# Vibration-Motor.net
KiCad netlist of a schematic drawn in Altium Designer
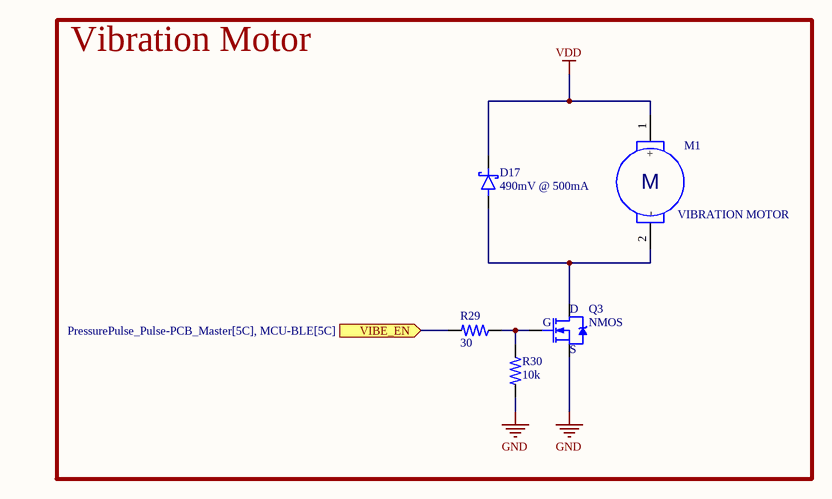
[diagram p0: Vibration-Motor.SchDoc]

(export (version "E")
  (design (tool "Eeschema 10.0.6"))
  (components
    (comp (ref "D17")
      (value "490mV @ 500mA")
      (footprint "PressurePulse:SOD-523")
      (fields (field (name "MFR") "Shikues"))
      (libsource (lib "PressurePulse") (part "SCHOTTKY DIODE"))
    )
    (comp (ref "M1")
      (value "VIBRATION MOTOR")
      (footprint "PressurePulse:BARE PADS - 2")
      (description "9000rpm Coin Type Vibration Motor 3V -  Vibration Motor ROHS")
      (fields (field (name "MFR") "LEADER"))
      (libsource (lib "PressurePulse") (part "VIBRATION MOTOR"))
    )
    (comp (ref "Q3")
      (value "NMOS")
      (footprint "PressurePulse:SOT-23")
      (description "100V 1.6A 1.3W 220mΩ@10V,1.6A N Channel SOT-23  MOSFETs ROHS")
      (fields (field (name "MFR") "Infineon"))
      (libsource (lib "PressurePulse") (part "NMOS"))
    )
    (comp (ref "R29")
      (value "30")
      (footprint "PressurePulse:0402R")
      (description "Resistor")
      (fields (field (name "Comment") "RES"))
      (libsource (lib "PressurePulse") (part "RES"))
    )
    (comp (ref "R30")
      (value "10k")
      (footprint "PressurePulse:0402R")
      (description "Resistor")
      (fields (field (name "Comment") "RES"))
      (libsource (lib "PressurePulse") (part "RES"))
    )
  )
  (nets
    (net (code "1") (name "/VIBE_EN") (class "Default")
      (node (ref "R29") (pin "2") (pinfunction "2_2") (pintype "passive"))
    )
    (net (code "2") (name "GND") (class "Default")
      (node (ref "Q3") (pin "S") (pinfunction "S_S") (pintype "passive"))
      (node (ref "R30") (pin "2") (pinfunction "2_2") (pintype "passive"))
    )
    (net (code "3") (name "Net-(M1--)") (class "Default")
      (node (ref "D17") (pin "A") (pinfunction "A_A") (pintype "passive"))
      (node (ref "M1") (pin "2") (pinfunction "-_2") (pintype "passive"))
      (node (ref "Q3") (pin "D") (pinfunction "D_D") (pintype "passive"))
    )
    (net (code "4") (name "Net-(Q3-PadG)") (class "Default")
      (node (ref "Q3") (pin "G") (pinfunction "G_G") (pintype "passive"))
      (node (ref "R29") (pin "1") (pinfunction "1_1") (pintype "passive"))
      (node (ref "R30") (pin "1") (pinfunction "1_1") (pintype "passive"))
    )
    (net (code "5") (name "VDD") (class "Default")
      (node (ref "D17") (pin "K") (pinfunction "K_K") (pintype "passive"))
      (node (ref "M1") (pin "1") (pinfunction "+_1") (pintype "passive"))
    )
  )
)
